# 4_channel_breakout.net
KiCad netlist of a schematic drawn in EAGLE
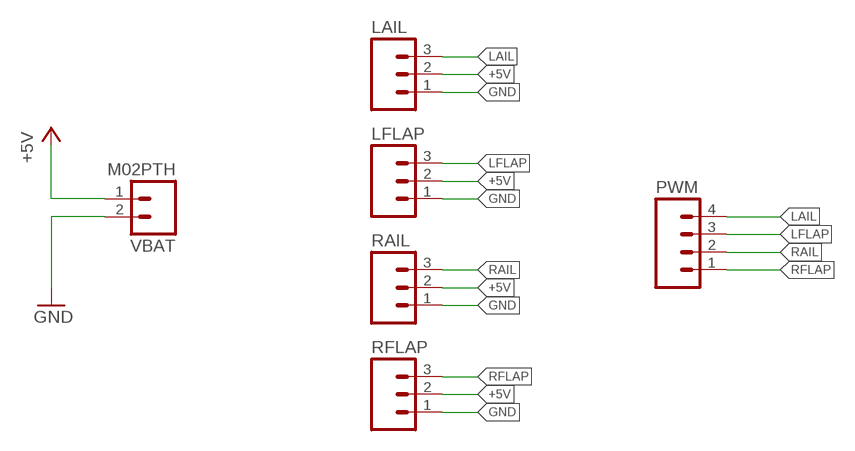
[diagram p0: schematic, sheet 1]

(export (version "E")
  (design (tool "Eeschema 10.0.6"))
  (components
    (comp (ref "LAIL")
      (value "M03LOCK")
      (footprint "eagle-import:1X03_LOCK")
      (libsource (lib "eagle-import") (part "M03LOCK"))
    )
    (comp (ref "LFLAP")
      (value "M03LOCK")
      (footprint "eagle-import:1X03_LOCK")
      (libsource (lib "eagle-import") (part "M03LOCK"))
    )
    (comp (ref "PWM")
      (value "M04PTH")
      (footprint "eagle-import:1X04")
      (libsource (lib "eagle-import") (part "M04PTH"))
    )
    (comp (ref "RAIL")
      (value "M03LOCK")
      (footprint "eagle-import:1X03_LOCK")
      (libsource (lib "eagle-import") (part "M03LOCK"))
    )
    (comp (ref "RFLAP")
      (value "M03LOCK")
      (footprint "eagle-import:1X03_LOCK")
      (libsource (lib "eagle-import") (part "M03LOCK"))
    )
    (comp (ref "VBAT")
      (value "M02PTH")
      (footprint "eagle-import:1X02")
      (libsource (lib "eagle-import") (part "M02PTH"))
    )
  )
  (nets
    (net (code "1") (name "+5V") (class "Default")
      (node (ref "LAIL") (pin "2") (pinfunction "2_2") (pintype "passive"))
      (node (ref "LFLAP") (pin "2") (pinfunction "2_2") (pintype "passive"))
      (node (ref "RAIL") (pin "2") (pinfunction "2_2") (pintype "passive"))
      (node (ref "RFLAP") (pin "2") (pinfunction "2_2") (pintype "passive"))
      (node (ref "VBAT") (pin "1") (pinfunction "1_1") (pintype "passive"))
    )
    (net (code "2") (name "GND") (class "Default")
      (node (ref "LAIL") (pin "1") (pinfunction "1_1") (pintype "passive"))
      (node (ref "LFLAP") (pin "1") (pinfunction "1_1") (pintype "passive"))
      (node (ref "RAIL") (pin "1") (pinfunction "1_1") (pintype "passive"))
      (node (ref "RFLAP") (pin "1") (pinfunction "1_1") (pintype "passive"))
      (node (ref "VBAT") (pin "2") (pinfunction "2_2") (pintype "passive"))
    )
    (net (code "3") (name "LAIL") (class "Default")
      (node (ref "LAIL") (pin "3") (pinfunction "3_3") (pintype "passive"))
      (node (ref "PWM") (pin "4") (pinfunction "4_4") (pintype "passive"))
    )
    (net (code "4") (name "LFLAP") (class "Default")
      (node (ref "LFLAP") (pin "3") (pinfunction "3_3") (pintype "passive"))
      (node (ref "PWM") (pin "3") (pinfunction "3_3") (pintype "passive"))
    )
    (net (code "5") (name "RAIL") (class "Default")
      (node (ref "PWM") (pin "2") (pinfunction "2_2") (pintype "passive"))
      (node (ref "RAIL") (pin "3") (pinfunction "3_3") (pintype "passive"))
    )
    (net (code "6") (name "RFLAP") (class "Default")
      (node (ref "PWM") (pin "1") (pinfunction "1_1") (pintype "passive"))
      (node (ref "RFLAP") (pin "3") (pinfunction "3_3") (pintype "passive"))
    )
  )
)
